# dc_sense.net
KiCad netlist of a schematic drawn in Altium Designer
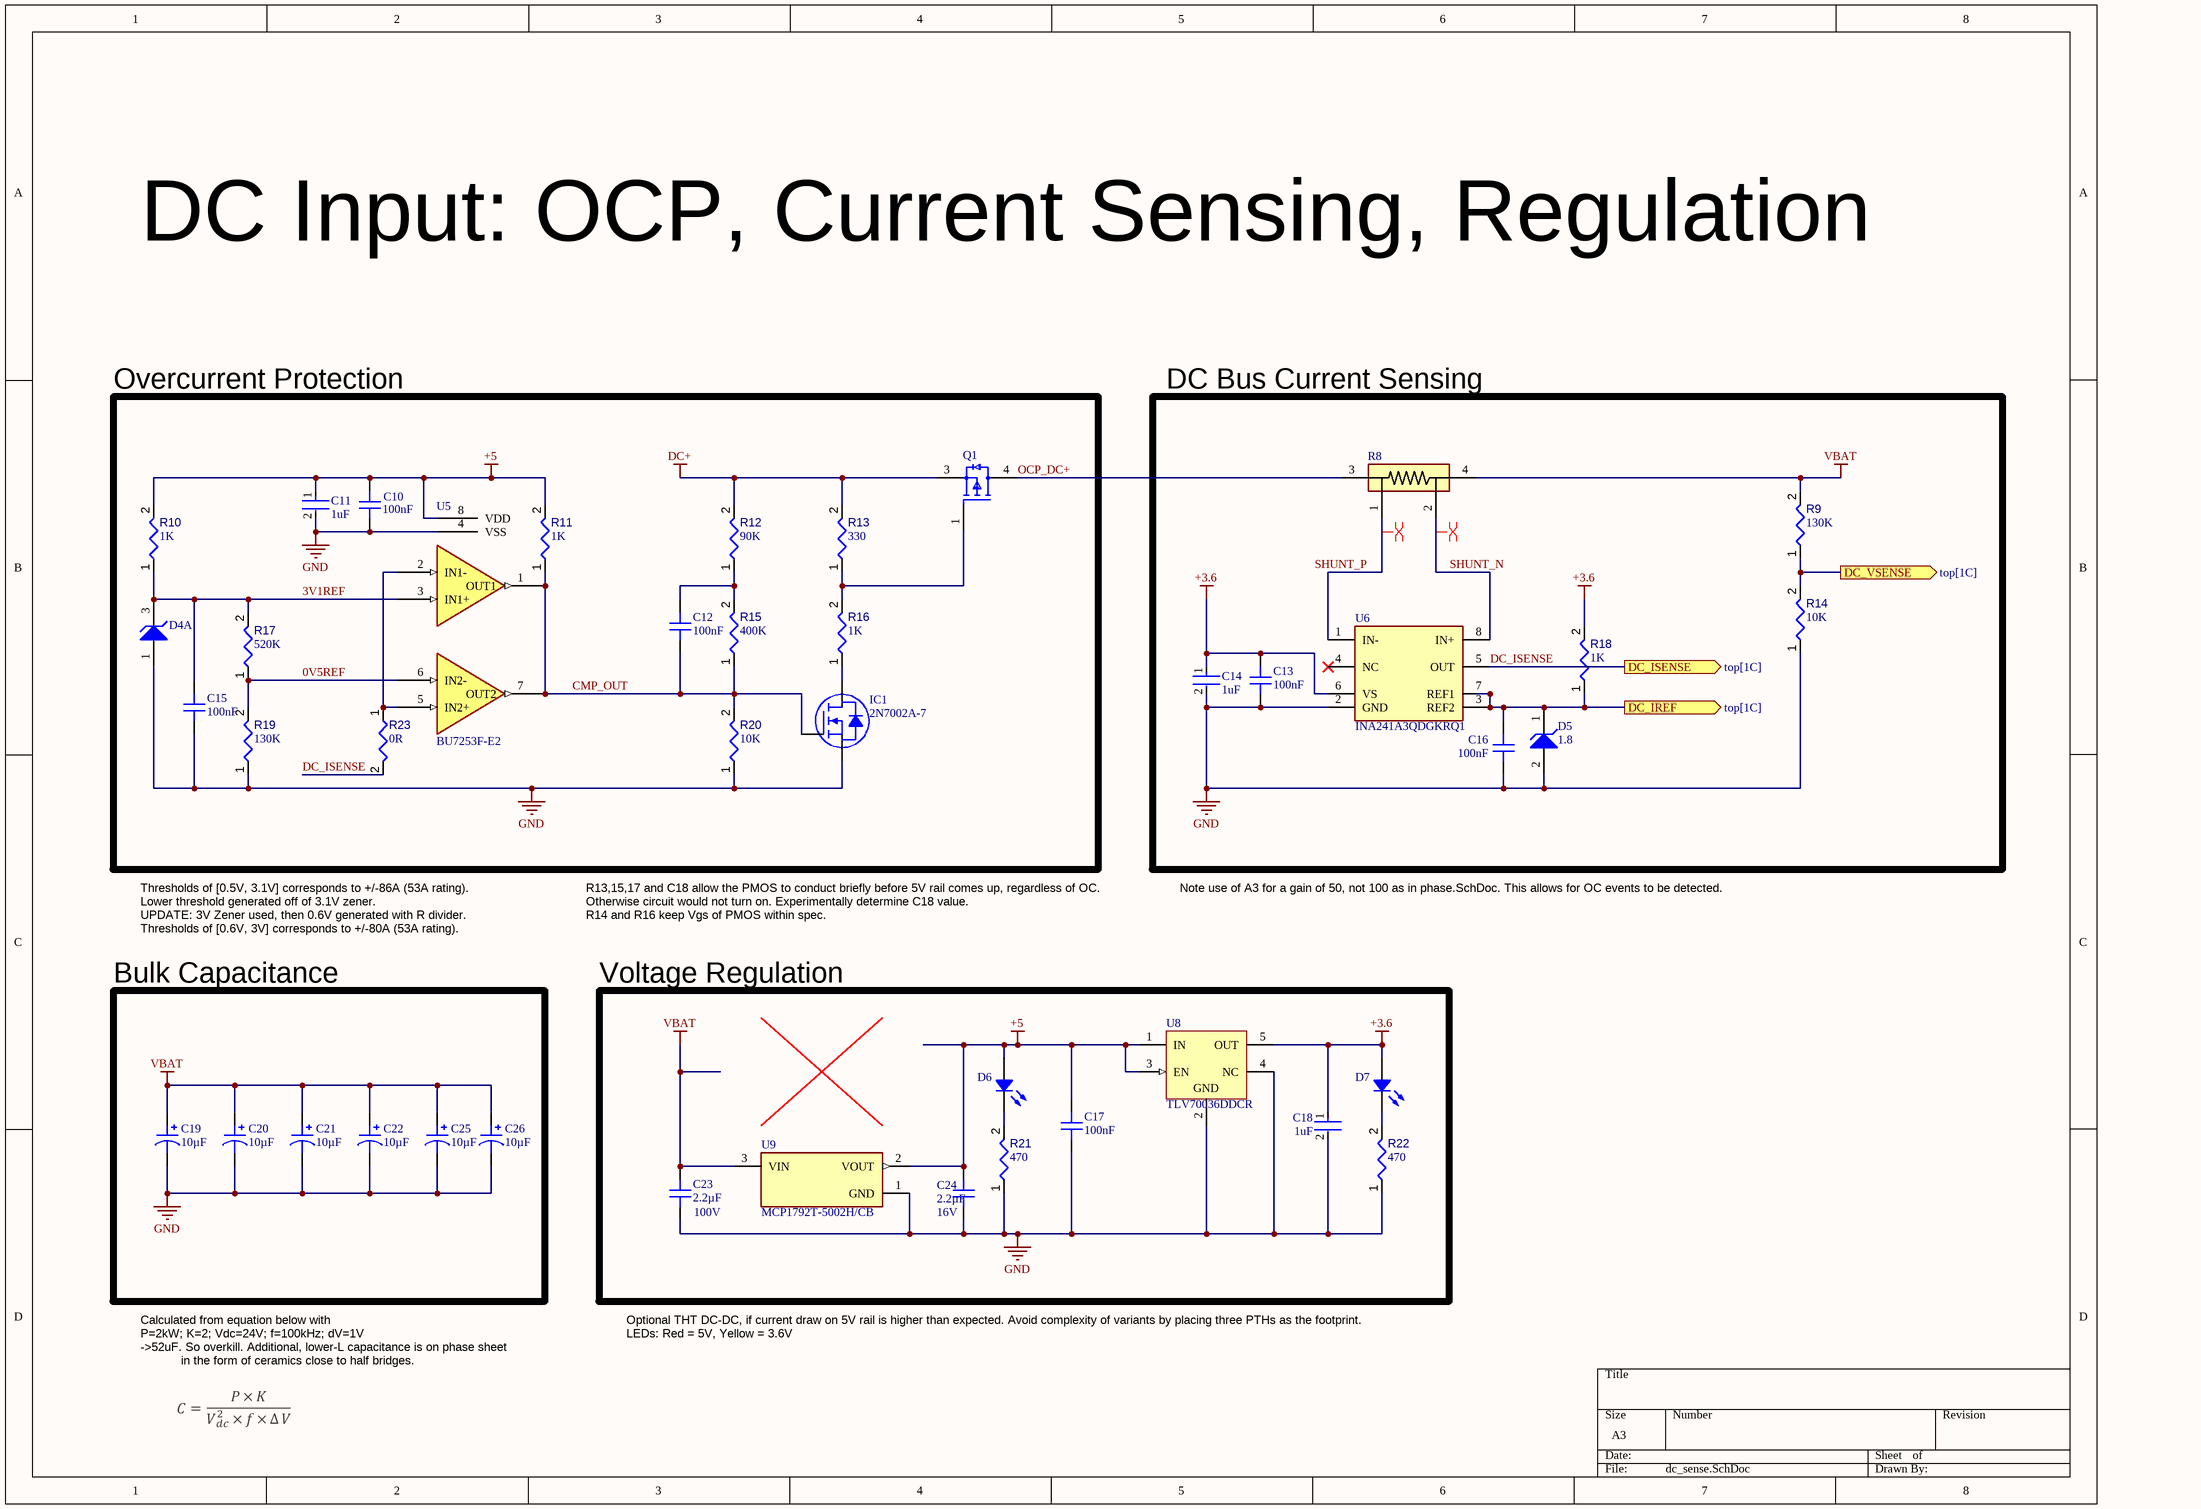
[diagram p0: dc_sense.SchDoc]

(export (version "E")
  (design (tool "Eeschema 10.0.6"))
  (components
    (comp (ref "C10")
      (value "100nF")
      (footprint "CAPC0402(1005)33_L")
      (description "CAP CER 0.1UF 16V X7R 0402")
      (fields
        (field (name "MANUFACTURER") "Samsung Electro-Mechanics")
        (field (name "PART NUMBER") "CL05B104KO5NNNC")
      )
      (libsource (lib "Americas- Northwestern Formula Racing- Northwestern University") (part "CAPACITOR"))
    )
    (comp (ref "C11")
      (value "1uF")
      (footprint "FP-GRM155-0_05-MFG")
      (description "Chip Multilayer Ceramic Capacitors for General Purpose, 0402, 1.0uF, B, 10%, 20%, 16V")
      (libsource (lib "Altium Content Vault") (part "02cd4be3c70576c341d710602a673aa"))
    )
    (comp (ref "C12")
      (value "100nF")
      (footprint "CAPC0402(1005)33_L")
      (description "CAP CER 0.1UF 16V X7R 0402")
      (fields
        (field (name "MANUFACTURER") "Samsung Electro-Mechanics")
        (field (name "PART NUMBER") "CL05B104KO5NNNC")
      )
      (libsource (lib "Americas- Northwestern Formula Racing- Northwestern University") (part "CAPACITOR"))
    )
    (comp (ref "C13")
      (value "100nF")
      (footprint "CAPC0402(1005)33_L")
      (description "CAP CER 0.1UF 16V X7R 0402")
      (fields
        (field (name "MANUFACTURER") "Samsung Electro-Mechanics")
        (field (name "PART NUMBER") "CL05B104KO5NNNC")
      )
      (libsource (lib "Americas- Northwestern Formula Racing- Northwestern University") (part "CAPACITOR"))
    )
    (comp (ref "C14")
      (value "1uF")
      (footprint "FP-GRM155-0_05-MFG")
      (description "Chip Multilayer Ceramic Capacitors for General Purpose, 0402, 1.0uF, B, 10%, 20%, 16V")
      (libsource (lib "Altium Content Vault") (part "02cd4be3c70576c341d710602a673aa"))
    )
    (comp (ref "C15")
      (value "100nF")
      (footprint "CAPC0402(1005)33_L")
      (description "CAP CER 0.1UF 16V X7R 0402")
      (fields
        (field (name "MANUFACTURER") "Samsung Electro-Mechanics")
        (field (name "PART NUMBER") "CL05B104KO5NNNC")
      )
      (libsource (lib "Americas- Northwestern Formula Racing- Northwestern University") (part "CAPACITOR"))
    )
    (comp (ref "C16")
      (value "100nF")
      (footprint "CAPC0402(1005)33_L")
      (description "CAP CER 0.1UF 16V X7R 0402")
      (fields
        (field (name "MANUFACTURER") "Samsung Electro-Mechanics")
        (field (name "PART NUMBER") "CL05B104KO5NNNC")
      )
      (libsource (lib "Americas- Northwestern Formula Racing- Northwestern University") (part "CAPACITOR"))
    )
    (comp (ref "C17")
      (value "100nF")
      (footprint "CAPC0402(1005)33_L")
      (description "CAP CER 0.1UF 16V X7R 0402")
      (fields
        (field (name "MANUFACTURER") "Samsung Electro-Mechanics")
        (field (name "PART NUMBER") "CL05B104KO5NNNC")
      )
      (libsource (lib "Americas- Northwestern Formula Racing- Northwestern University") (part "CAPACITOR"))
    )
    (comp (ref "C18")
      (value "1uF")
      (footprint "FP-GRM155-0_05-MFG")
      (description "Chip Multilayer Ceramic Capacitors for General Purpose, 0402, 1.0uF, B, 10%, 20%, 16V")
      (libsource (lib "Altium Content Vault") (part "02cd4be3c70576c341d710602a673aa"))
    )
    (comp (ref "C19")
      (value "10µF")
      (footprint "CAP ALSMD 8.3MM H10.5MM")
      (description "CAP ALUM 10UF 20% 100V SMD")
      (fields (field (name "TOLERANCE") "20%") (field (name "PART NUMBER") "UUX2A100MNL1GS"))
      (libsource (lib "Americas- Northwestern Formula Racing- Northwestern University") (part "POLARISED CAPACITOR"))
    )
    (comp (ref "C20")
      (value "10µF")
      (footprint "CAP ALSMD 8.3MM H10.5MM")
      (description "CAP ALUM 10UF 20% 100V SMD")
      (fields (field (name "TOLERANCE") "20%") (field (name "PART NUMBER") "UUX2A100MNL1GS"))
      (libsource (lib "Americas- Northwestern Formula Racing- Northwestern University") (part "POLARISED CAPACITOR"))
    )
    (comp (ref "C21")
      (value "10µF")
      (footprint "CAP ALSMD 8.3MM H10.5MM")
      (description "CAP ALUM 10UF 20% 100V SMD")
      (fields (field (name "TOLERANCE") "20%") (field (name "PART NUMBER") "UUX2A100MNL1GS"))
      (libsource (lib "Americas- Northwestern Formula Racing- Northwestern University") (part "POLARISED CAPACITOR"))
    )
    (comp (ref "C22")
      (value "10µF")
      (footprint "CAP ALSMD 8.3MM H10.5MM")
      (description "CAP ALUM 10UF 20% 100V SMD")
      (fields (field (name "TOLERANCE") "20%") (field (name "PART NUMBER") "UUX2A100MNL1GS"))
      (libsource (lib "Americas- Northwestern Formula Racing- Northwestern University") (part "POLARISED CAPACITOR"))
    )
    (comp (ref "C23")
      (value "2.2µF")
      (footprint "CAP 1206_3216 - 0.8MM")
      (description "CAP CER 2.2UF 100V X7R 1206")
      (fields
        (field (name "MANUFACTURER") "Yageo")
        (field (name "TOLERANCE") "10%")
        (field (name "VOLTAGE - RATED") "100V")
      )
      (libsource (lib "Americas- Northwestern Formula Racing- Northwestern University") (part "CAPACITOR"))
    )
    (comp (ref "C24")
      (value "2.2µF")
      (footprint "CAP 0603_1608")
      (description "CAP CER 2.2UF 16V X5R 0603")
      (fields
        (field (name "PART NUMBER") "KGM15BR51C225KM")
        (field (name "TOLERANCE") "10%")
        (field (name "VOLTAGE - RATED") "16V")
      )
      (libsource (lib "Americas- Northwestern Formula Racing- Northwestern University") (part "CAPACITOR"))
    )
    (comp (ref "C25")
      (value "10µF")
      (footprint "CAP ALSMD 8.3MM H10.5MM")
      (description "CAP ALUM 10UF 20% 100V SMD")
      (fields (field (name "TOLERANCE") "20%") (field (name "PART NUMBER") "UUX2A100MNL1GS"))
      (libsource (lib "Americas- Northwestern Formula Racing- Northwestern University") (part "POLARISED CAPACITOR"))
    )
    (comp (ref "C26")
      (value "10µF")
      (footprint "CAP ALSMD 8.3MM H10.5MM")
      (description "CAP ALUM 10UF 20% 100V SMD")
      (fields (field (name "TOLERANCE") "20%") (field (name "PART NUMBER") "UUX2A100MNL1GS"))
      (libsource (lib "Americas- Northwestern Formula Racing- Northwestern University") (part "POLARISED CAPACITOR"))
    )
    (comp (ref "D4")
      (value "SZBZX84C3V0ET1G")
      (footprint "ONSC-SOT-23-3-318-08_V")
      (description "Zener Voltage Regulator, 225 mW, 3-Pin SOT-23, Pb-Free, Tape and Reel")
      (fields (field (name "MANUFACTURER") "On Semiconductor"))
      (libsource (lib "Altium Content Vault") (part "ONSC-A1K3-3"))
    )
    (comp (ref "D5")
      (value "SZMMSZ4678T1G")
      (footprint "ONSC-SOD-123-2-425-04_V")
      (description "Zener Voltage Regulator, 500 mW, 2-Pin SOD-123, Pb-Free, Tape and Reel")
      (fields (field (name "VZ TYP (V)") "1.8") (field (name "MANUFACTURER") "On Semiconductor"))
      (libsource (lib "Altium Content Vault") (part "ONSC-K1A2-2"))
    )
    (comp (ref "D6")
      (value "150060BS55040")
      (footprint "LED 0603_1608 BLUE")
      (description "LED BLUE DIFFUSED 0603 SMD")
      (fields (field (name "MANUFACTURER") "Würth Elektronik"))
      (libsource (lib "Americas- Northwestern Formula Racing- Northwestern University") (part "LED"))
    )
    (comp (ref "D7")
      (value "150060BS55040")
      (footprint "LED 0603_1608 BLUE")
      (description "LED BLUE DIFFUSED 0603 SMD")
      (fields (field (name "MANUFACTURER") "Würth Elektronik"))
      (libsource (lib "Americas- Northwestern Formula Racing- Northwestern University") (part "LED"))
    )
    (comp (ref "IC1")
      (value "2N7002A-7")
      (footprint "DIODES SOT-23-3")
      (description "MOSFET N-CH 60V 180MA SOT23")
      (fields (field (name "MANUFACTURER") "Diodes Incorporated"))
      (libsource (lib "Americas- Northwestern Formula Racing- Northwestern University") (part "DIODES INC MOSFET N-CH SOT-23-3"))
    )
    (comp (ref "Q1")
      (value "SQM100P10-19L_GE3")
      (footprint "FP-T13-0707-MFG")
      (description "MOSFET P-CH 100V 93A TO263")
      (libsource (lib "Altium Content Vault") (part "b7367ac3e8978bf9cd3938efe1e00f9"))
    )
    (comp (ref "R8")
      (value "PU2726FKMPD0U3L")
      (footprint "PU2726FKMPD0U3L")
      (description "Thick Film Resistors - SMD 0.3mOhms 11W 2726 1% 75ppm Shunt AEC-Q200")
      (libsource (lib "Americas- Northwestern Formula Racing- Northwestern University") (part "PU2726FKMPD0U3L"))
    )
    (comp (ref "R9")
      (value "130K")
      (footprint "RESC0603(1608)_L")
      (description "120R 0.1W 5% 0603 (1608 Metric)  SMD")
      (fields (field (name "POWER") "100mW") (field (name "TOLERANCE") "5%"))
      (libsource (lib "Americas- Northwestern Formula Racing- Northwestern University") (part "120R3J"))
    )
    (comp (ref "R10")
      (value "1K")
      (footprint "RESC0603(1608)_L")
      (description "120R 0.1W 5% 0603 (1608 Metric)  SMD")
      (fields (field (name "POWER") "100mW") (field (name "TOLERANCE") "5%"))
      (libsource (lib "Americas- Northwestern Formula Racing- Northwestern University") (part "120R3J"))
    )
    (comp (ref "R11")
      (value "1K")
      (footprint "RESC0603(1608)_L")
      (description "120R 0.1W 5% 0603 (1608 Metric)  SMD")
      (fields (field (name "POWER") "100mW") (field (name "TOLERANCE") "5%"))
      (libsource (lib "Americas- Northwestern Formula Racing- Northwestern University") (part "120R3J"))
    )
    (comp (ref "R12")
      (value "90K")
      (footprint "RESC0603(1608)_L")
      (description "120R 0.1W 5% 0603 (1608 Metric)  SMD")
      (fields (field (name "POWER") "100mW") (field (name "TOLERANCE") "5%"))
      (libsource (lib "Americas- Northwestern Formula Racing- Northwestern University") (part "120R3J"))
    )
    (comp (ref "R13")
      (value "330")
      (footprint "RESC0603(1608)_L")
      (description "120R 0.1W 5% 0603 (1608 Metric)  SMD")
      (fields (field (name "POWER") "100mW") (field (name "TOLERANCE") "5%"))
      (libsource (lib "Americas- Northwestern Formula Racing- Northwestern University") (part "120R3J"))
    )
    (comp (ref "R14")
      (value "10K")
      (footprint "RESC0603(1608)_L")
      (description "120R 0.1W 5% 0603 (1608 Metric)  SMD")
      (fields (field (name "POWER") "100mW") (field (name "TOLERANCE") "5%"))
      (libsource (lib "Americas- Northwestern Formula Racing- Northwestern University") (part "120R3J"))
    )
    (comp (ref "R15")
      (value "400K")
      (footprint "RESC0603(1608)_L")
      (description "120R 0.1W 5% 0603 (1608 Metric)  SMD")
      (fields (field (name "POWER") "100mW") (field (name "TOLERANCE") "5%"))
      (libsource (lib "Americas- Northwestern Formula Racing- Northwestern University") (part "120R3J"))
    )
    (comp (ref "R16")
      (value "1K")
      (footprint "RESC0603(1608)_L")
      (description "120R 0.1W 5% 0603 (1608 Metric)  SMD")
      (fields (field (name "POWER") "100mW") (field (name "TOLERANCE") "5%"))
      (libsource (lib "Americas- Northwestern Formula Racing- Northwestern University") (part "120R3J"))
    )
    (comp (ref "R17")
      (value "520K")
      (footprint "RESC0603(1608)_L")
      (description "120R 0.1W 5% 0603 (1608 Metric)  SMD")
      (fields (field (name "POWER") "100mW") (field (name "TOLERANCE") "5%"))
      (libsource (lib "Americas- Northwestern Formula Racing- Northwestern University") (part "120R3J"))
    )
    (comp (ref "R18")
      (value "1K")
      (footprint "RESC0603(1608)_L")
      (description "120R 0.1W 5% 0603 (1608 Metric)  SMD")
      (fields (field (name "POWER") "100mW") (field (name "TOLERANCE") "5%"))
      (libsource (lib "Americas- Northwestern Formula Racing- Northwestern University") (part "120R3J"))
    )
    (comp (ref "R19")
      (value "130K")
      (footprint "RESC0603(1608)_L")
      (description "120R 0.1W 5% 0603 (1608 Metric)  SMD")
      (fields (field (name "POWER") "100mW") (field (name "TOLERANCE") "5%"))
      (libsource (lib "Americas- Northwestern Formula Racing- Northwestern University") (part "120R3J"))
    )
    (comp (ref "R20")
      (value "10K")
      (footprint "RESC0603(1608)_L")
      (description "120R 0.1W 5% 0603 (1608 Metric)  SMD")
      (fields (field (name "POWER") "100mW") (field (name "TOLERANCE") "5%"))
      (libsource (lib "Americas- Northwestern Formula Racing- Northwestern University") (part "120R3J"))
    )
    (comp (ref "R21")
      (value "470")
      (footprint "RESC0603(1608)_L")
      (description "120R 0.1W 5% 0603 (1608 Metric)  SMD")
      (fields (field (name "POWER") "100mW") (field (name "TOLERANCE") "5%"))
      (libsource (lib "Americas- Northwestern Formula Racing- Northwestern University") (part "120R3J"))
    )
    (comp (ref "R22")
      (value "470")
      (footprint "RESC0603(1608)_L")
      (description "120R 0.1W 5% 0603 (1608 Metric)  SMD")
      (fields (field (name "POWER") "100mW") (field (name "TOLERANCE") "5%"))
      (libsource (lib "Americas- Northwestern Formula Racing- Northwestern University") (part "120R3J"))
    )
    (comp (ref "R23")
      (value "0R")
      (footprint "RESC0603(1608)_L")
      (description "120R 0.1W 5% 0603 (1608 Metric)  SMD")
      (fields (field (name "POWER") "100mW") (field (name "TOLERANCE") "5%"))
      (libsource (lib "Americas- Northwestern Formula Racing- Northwestern University") (part "120R3J"))
    )
    (comp (ref "U5")
      (value "BU7253F-E2")
      (footprint "SOP8_ROM")
      (description "Comparator, Open Drain, 5V")
      (libsource (lib "Americas- Northwestern Formula Racing- Northwestern University") (part "BU7253F-E2"))
    )
    (comp (ref "U6")
      (value "INA241A3QDGKRQ1")
      (footprint "SOIC127P600X175-8N")
      (fields (field (name "MOUSER PART NUMBER") "595-INA241A3QDGKRQ1"))
      (libsource (lib "Americas- Northwestern Formula Racing- Northwestern University") (part "Copy of INA241A4QDGKRQ1"))
    )
    (comp (ref "U8")
      (value "TLV70036DDCR")
      (footprint "DDC0005A_L")
      (fields (field (name "MANUFACTURER") "Texas Instruments"))
      (libsource (lib "Altium Content Vault") (part "TI-TXX7XXXX-5"))
    )
    (comp (ref "U9")
      (value "MCP1792T-5002H/CB")
      (footprint "FP-C04-130-IPC_C")
      (description "IC REG LINEAR 5V 100MA SOT23A-3")
      (libsource (lib "Altium Content Vault") (part "bd94623faa3c699494368a50adf163b"))
    )
  )
  (nets
    (net (code "1") (name "+3.6") (class "Default")
      (node (ref "C13") (pin "2") (pinfunction "2_2") (pintype "passive"))
      (node (ref "C14") (pin "1") (pinfunction "1_1") (pintype "passive"))
      (node (ref "C18") (pin "1") (pinfunction "1_1") (pintype "passive"))
      (node (ref "D7") (pin "1") (pinfunction "1_1") (pintype "passive"))
      (node (ref "R18") (pin "2") (pinfunction "2_2") (pintype "passive"))
      (node (ref "U6") (pin "6") (pinfunction "VS_6") (pintype "passive"))
      (node (ref "U8") (pin "5") (pinfunction "OUT_5") (pintype "power_in"))
    )
    (net (code "2") (name "+5") (class "Default")
      (node (ref "C10") (pin "2") (pinfunction "2_2") (pintype "passive"))
      (node (ref "C11") (pin "1") (pinfunction "1_1") (pintype "passive"))
      (node (ref "C17") (pin "2") (pinfunction "2_2") (pintype "passive"))
      (node (ref "C24") (pin "2") (pinfunction "2_2") (pintype "passive"))
      (node (ref "D6") (pin "1") (pinfunction "1_1") (pintype "passive"))
      (node (ref "R10") (pin "2") (pinfunction "2_2") (pintype "passive"))
      (node (ref "R11") (pin "2") (pinfunction "2_2") (pintype "passive"))
      (node (ref "U5") (pin "8") (pinfunction "VDD_8") (pintype "power_in"))
      (node (ref "U8") (pin "1") (pinfunction "IN_1") (pintype "power_in"))
      (node (ref "U8") (pin "3") (pinfunction "EN_3") (pintype "input"))
      (node (ref "U9") (pin "2") (pinfunction "VOUT_2") (pintype "output"))
    )
    (net (code "3") (name "/0V5REF") (class "Default")
      (node (ref "R17") (pin "1") (pinfunction "1_1") (pintype "passive"))
      (node (ref "R19") (pin "2") (pinfunction "2_2") (pintype "passive"))
      (node (ref "U5") (pin "6") (pinfunction "IN2-_6") (pintype "input"))
    )
    (net (code "4") (name "/3V1REF") (class "Default")
      (node (ref "C15") (pin "2") (pinfunction "2_2") (pintype "passive"))
      (node (ref "D4") (pin "3") (pinfunction "K_3") (pintype "passive"))
      (node (ref "R10") (pin "1") (pinfunction "1_1") (pintype "passive"))
      (node (ref "R17") (pin "2") (pinfunction "2_2") (pintype "passive"))
      (node (ref "U5") (pin "3") (pinfunction "IN1+_3") (pintype "input"))
    )
    (net (code "5") (name "/CMP_OUT") (class "Default")
      (node (ref "C12") (pin "1") (pinfunction "1_1") (pintype "passive"))
      (node (ref "IC1") (pin "1") (pinfunction "G_1") (pintype "passive"))
      (node (ref "R11") (pin "1") (pinfunction "1_1") (pintype "passive"))
      (node (ref "R15") (pin "1") (pinfunction "1_1") (pintype "passive"))
      (node (ref "R20") (pin "2") (pinfunction "2_2") (pintype "passive"))
      (node (ref "U5") (pin "1") (pinfunction "OUT1_1") (pintype "output"))
      (node (ref "U5") (pin "7") (pinfunction "OUT2_7") (pintype "output"))
    )
    (net (code "6") (name "/DC_IREF") (class "Default")
      (node (ref "C16") (pin "2") (pinfunction "2_2") (pintype "passive"))
      (node (ref "D5") (pin "1") (pinfunction "K_1") (pintype "passive"))
      (node (ref "R18") (pin "1") (pinfunction "1_1") (pintype "passive"))
      (node (ref "U6") (pin "3") (pinfunction "REF2_3") (pintype "passive"))
      (node (ref "U6") (pin "7") (pinfunction "REF1_7") (pintype "passive"))
    )
    (net (code "7") (name "/DC_ISENSE") (class "Default")
      (node (ref "R23") (pin "2") (pinfunction "2_2") (pintype "passive"))
      (node (ref "U6") (pin "5") (pinfunction "OUT_5") (pintype "passive"))
    )
    (net (code "8") (name "/DC_VSENSE") (class "Default")
      (node (ref "R14") (pin "2") (pinfunction "2_2") (pintype "passive"))
      (node (ref "R9") (pin "1") (pinfunction "1_1") (pintype "passive"))
    )
    (net (code "9") (name "/OCP_DC+") (class "Default")
      (node (ref "Q1") (pin "4") (pinfunction "D_4") (pintype "passive"))
      (node (ref "R8") (pin "3") (pinfunction "3_3") (pintype "passive"))
    )
    (net (code "10") (name "/SHUNT_N") (class "Default")
      (node (ref "R8") (pin "2") (pinfunction "2_2") (pintype "passive"))
      (node (ref "U6") (pin "8") (pinfunction "IN+_8") (pintype "passive"))
    )
    (net (code "11") (name "/SHUNT_P") (class "Default")
      (node (ref "R8") (pin "1") (pinfunction "1_1") (pintype "passive"))
      (node (ref "U6") (pin "1") (pinfunction "IN-_1") (pintype "passive"))
    )
    (net (code "12") (name "DC+") (class "Default")
      (node (ref "Q1") (pin "3") (pinfunction "S_3") (pintype "passive"))
      (node (ref "R12") (pin "2") (pinfunction "2_2") (pintype "passive"))
      (node (ref "R13") (pin "2") (pinfunction "2_2") (pintype "passive"))
    )
    (net (code "13") (name "GND") (class "Default")
      (node (ref "C10") (pin "1") (pinfunction "1_1") (pintype "passive"))
      (node (ref "C11") (pin "2") (pinfunction "2_2") (pintype "passive"))
      (node (ref "C13") (pin "1") (pinfunction "1_1") (pintype "passive"))
      (node (ref "C14") (pin "2") (pinfunction "2_2") (pintype "passive"))
      (node (ref "C15") (pin "1") (pinfunction "1_1") (pintype "passive"))
      (node (ref "C16") (pin "1") (pinfunction "1_1") (pintype "passive"))
      (node (ref "C17") (pin "1") (pinfunction "1_1") (pintype "passive"))
      (node (ref "C18") (pin "2") (pinfunction "2_2") (pintype "passive"))
      (node (ref "C19") (pin "2") (pinfunction "2_2") (pintype "passive"))
      (node (ref "C20") (pin "2") (pinfunction "2_2") (pintype "passive"))
      (node (ref "C21") (pin "2") (pinfunction "2_2") (pintype "passive"))
      (node (ref "C22") (pin "2") (pinfunction "2_2") (pintype "passive"))
      (node (ref "C23") (pin "1") (pinfunction "1_1") (pintype "passive"))
      (node (ref "C24") (pin "1") (pinfunction "1_1") (pintype "passive"))
      (node (ref "C25") (pin "2") (pinfunction "2_2") (pintype "passive"))
      (node (ref "C26") (pin "2") (pinfunction "2_2") (pintype "passive"))
      (node (ref "D4") (pin "1") (pinfunction "A_1") (pintype "passive"))
      (node (ref "D5") (pin "2") (pinfunction "A_2") (pintype "passive"))
      (node (ref "IC1") (pin "2") (pinfunction "S_2") (pintype "passive"))
      (node (ref "R14") (pin "1") (pinfunction "1_1") (pintype "passive"))
      (node (ref "R19") (pin "1") (pinfunction "1_1") (pintype "passive"))
      (node (ref "R20") (pin "1") (pinfunction "1_1") (pintype "passive"))
      (node (ref "R21") (pin "1") (pinfunction "1_1") (pintype "passive"))
      (node (ref "R22") (pin "1") (pinfunction "1_1") (pintype "passive"))
      (node (ref "U5") (pin "4") (pinfunction "VSS_4") (pintype "power_in"))
      (node (ref "U6") (pin "2") (pinfunction "GND_2") (pintype "passive"))
      (node (ref "U8") (pin "2") (pinfunction "GND_2") (pintype "power_in"))
      (node (ref "U8") (pin "4") (pinfunction "NC_4") (pintype "passive"))
      (node (ref "U9") (pin "1") (pinfunction "GND_1") (pintype "power_in"))
    )
    (net (code "14") (name "Net-(C12-Pad2)") (class "Default")
      (node (ref "C12") (pin "2") (pinfunction "2_2") (pintype "passive"))
      (node (ref "R12") (pin "1") (pinfunction "1_1") (pintype "passive"))
      (node (ref "R15") (pin "2") (pinfunction "2_2") (pintype "passive"))
    )
    (net (code "15") (name "Net-(D6-Pad2)") (class "Default")
      (node (ref "D6") (pin "2") (pinfunction "2_2") (pintype "passive"))
      (node (ref "R21") (pin "2") (pinfunction "2_2") (pintype "passive"))
    )
    (net (code "16") (name "Net-(D7-Pad2)") (class "Default")
      (node (ref "D7") (pin "2") (pinfunction "2_2") (pintype "passive"))
      (node (ref "R22") (pin "2") (pinfunction "2_2") (pintype "passive"))
    )
    (net (code "17") (name "Net-(IC1-D)") (class "Default")
      (node (ref "IC1") (pin "3") (pinfunction "D_3") (pintype "passive"))
      (node (ref "R16") (pin "1") (pinfunction "1_1") (pintype "passive"))
    )
    (net (code "18") (name "Net-(Q1-G)") (class "Default")
      (node (ref "Q1") (pin "1") (pinfunction "G_1") (pintype "passive"))
      (node (ref "R13") (pin "1") (pinfunction "1_1") (pintype "passive"))
      (node (ref "R16") (pin "2") (pinfunction "2_2") (pintype "passive"))
    )
    (net (code "19") (name "Net-(U5-IN1-)") (class "Default")
      (node (ref "R23") (pin "1") (pinfunction "1_1") (pintype "passive"))
      (node (ref "U5") (pin "2") (pinfunction "IN1-_2") (pintype "input"))
      (node (ref "U5") (pin "5") (pinfunction "IN2+_5") (pintype "input"))
    )
    (net (code "20") (name "VBAT") (class "Default")
      (node (ref "C19") (pin "1") (pinfunction "1_1") (pintype "passive"))
      (node (ref "C20") (pin "1") (pinfunction "1_1") (pintype "passive"))
      (node (ref "C21") (pin "1") (pinfunction "1_1") (pintype "passive"))
      (node (ref "C22") (pin "1") (pinfunction "1_1") (pintype "passive"))
      (node (ref "C23") (pin "2") (pinfunction "2_2") (pintype "passive"))
      (node (ref "C25") (pin "1") (pinfunction "1_1") (pintype "passive"))
      (node (ref "C26") (pin "1") (pinfunction "1_1") (pintype "passive"))
      (node (ref "R8") (pin "4") (pinfunction "4_4") (pintype "passive"))
      (node (ref "R9") (pin "2") (pinfunction "2_2") (pintype "passive"))
      (node (ref "U9") (pin "3") (pinfunction "VIN_3") (pintype "power_in"))
    )
    (net (code "21") (name "unconnected-(U6-NC-Pad4)") (class "Default")
      (node (ref "U6") (pin "4") (pinfunction "NC_4") (pintype "passive+no_connect"))
    )
  )
)
